# SCH_Blinking-led-tree-555_2025-11-29.net
KiCad netlist of a schematic drawn in EasyEDA
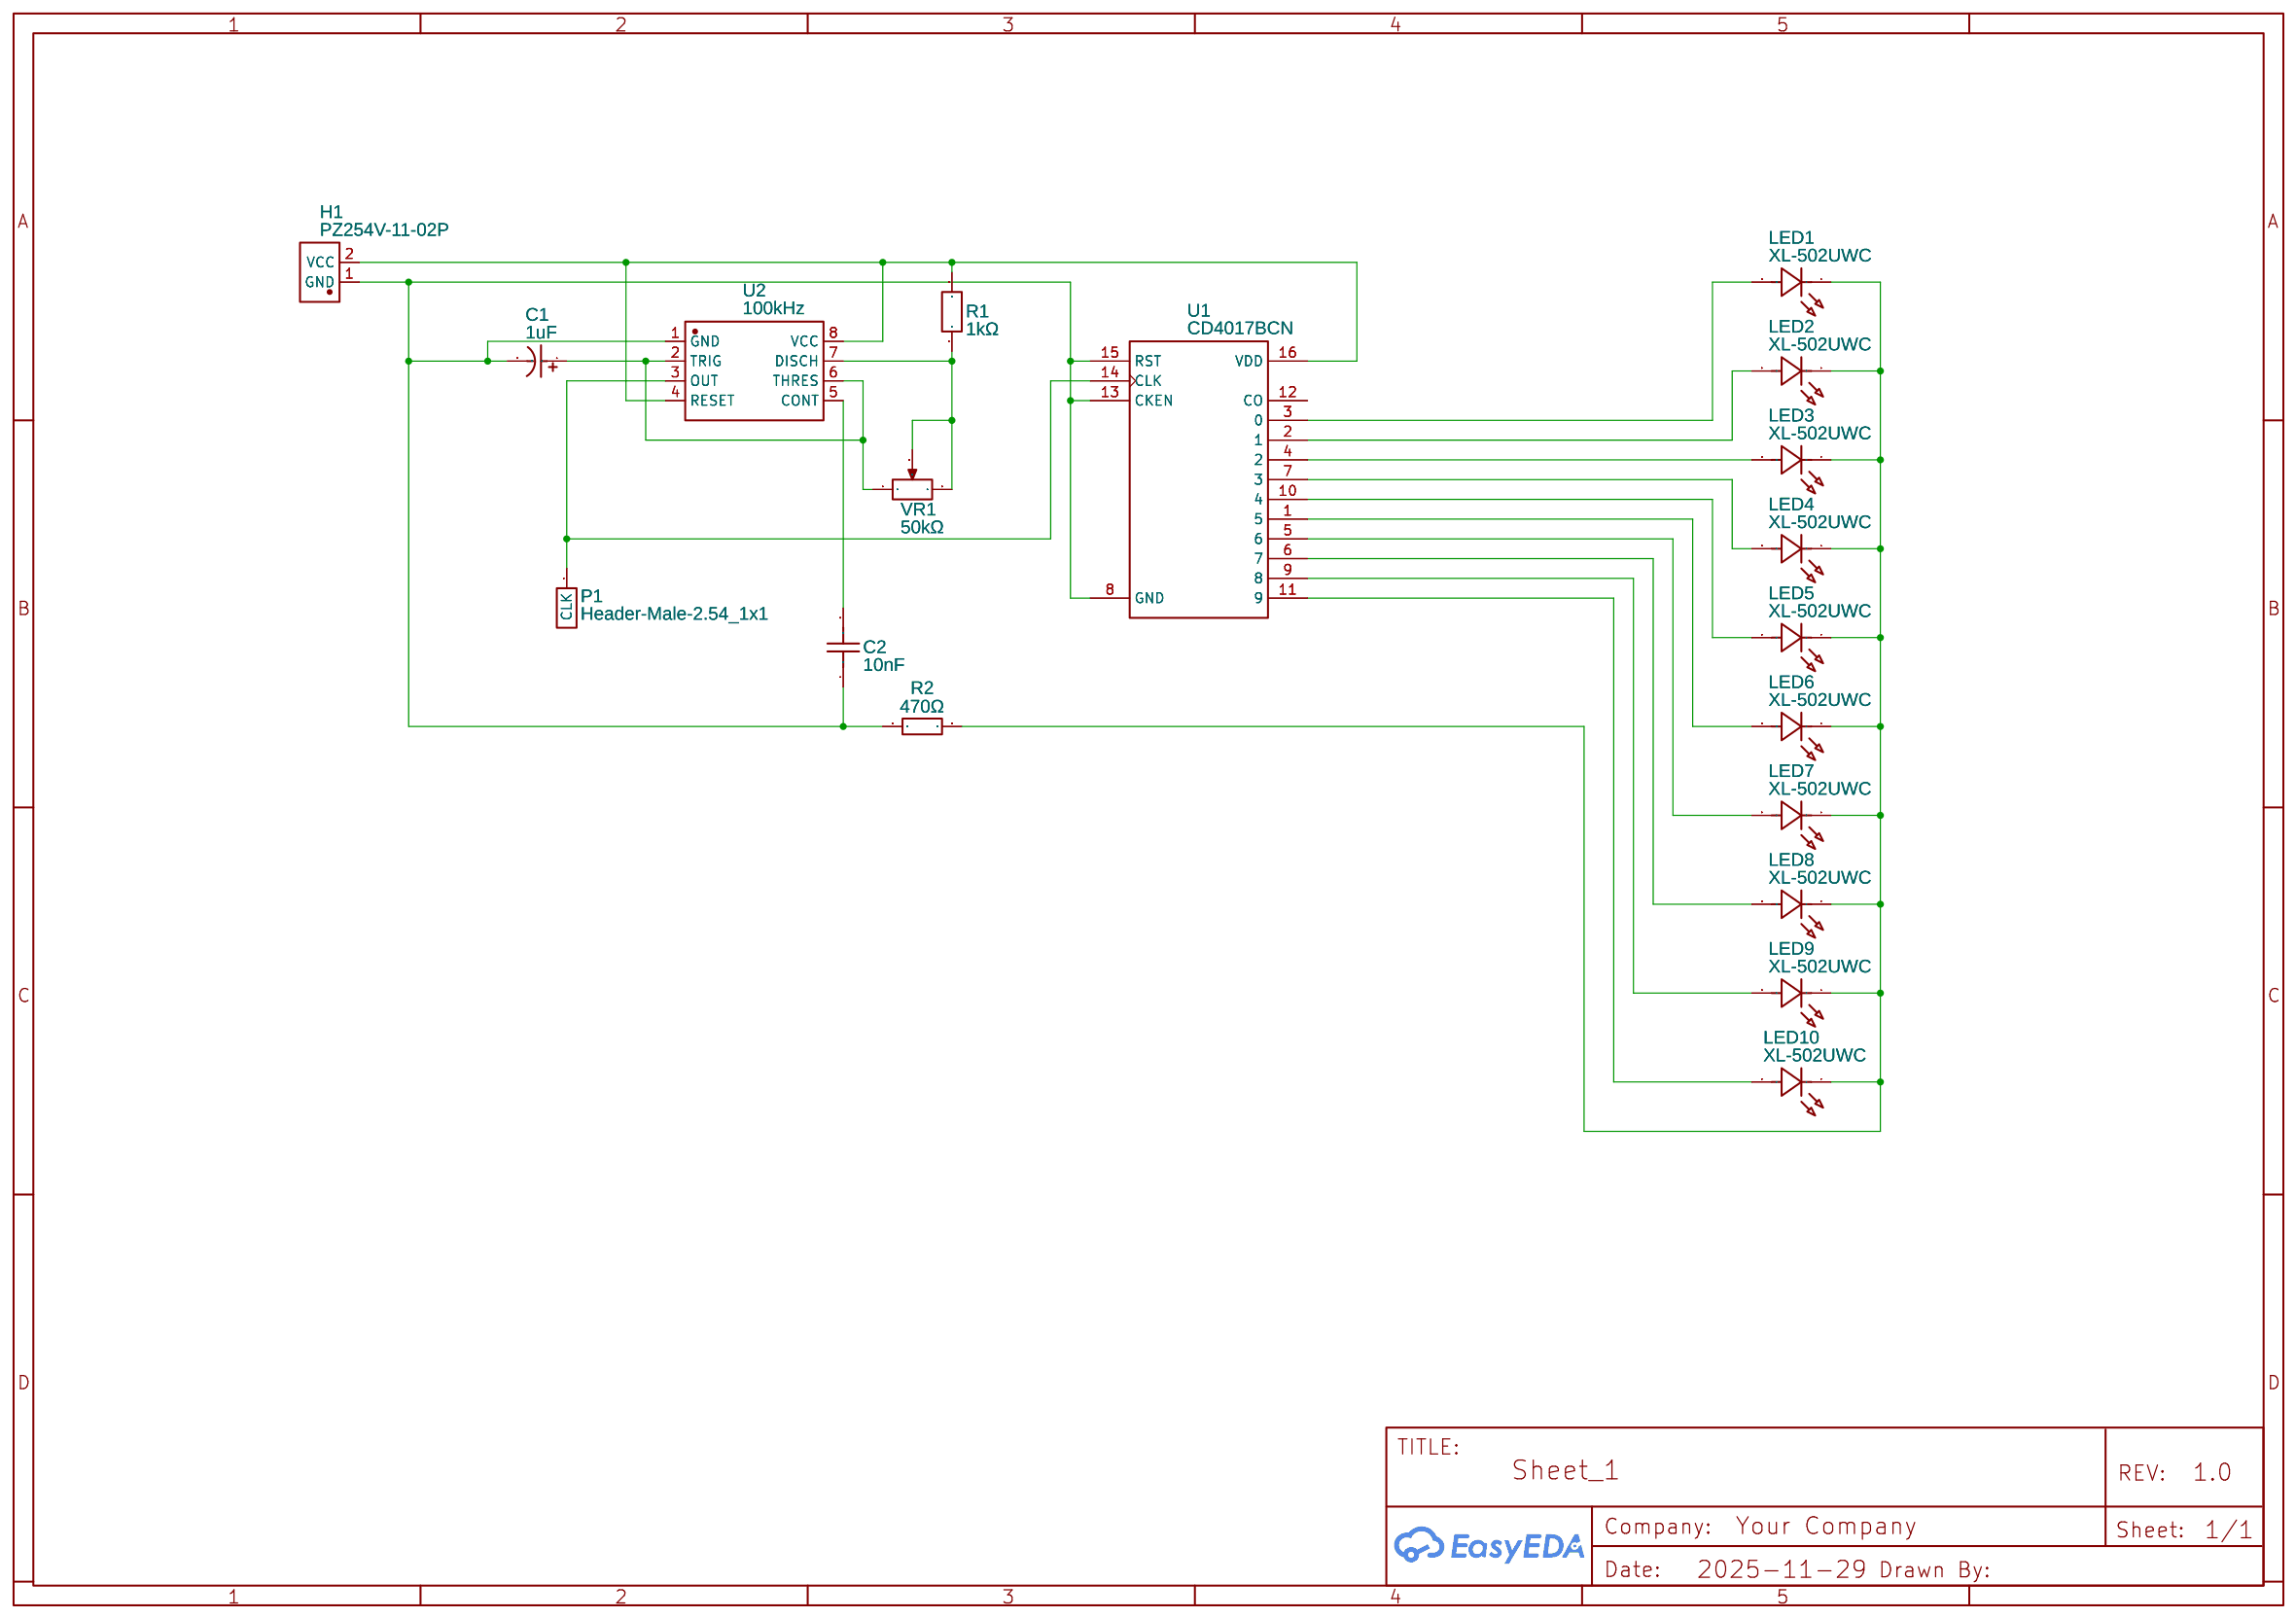
[diagram p0: schematic sheet]

(export (version "E")
  (design (tool "Eeschema 10.0.6"))
  (components
    (comp (ref "C1")
      (value "1uF")
      (fields (field (name "Manufacturer Part") "KF010M050C110A") (field (name "Manufacturer") "CapXon(丰宾)"))
      (libsource (lib "") (part "KF010M050C110A"))
    )
    (comp (ref "C2")
      (value "10nF")
      (fields (field (name "Manufacturer Part") "N09F1B103MN0B0S0N0") (field (name "Manufacturer") "STE(松田)"))
      (libsource (lib "") (part "N09F1B103MN0B0S0N0"))
    )
    (comp (ref "H1")
      (value "PZ254V-11-02P")
      (fields (field (name "Manufacturer") "XFCN(兴飞)"))
      (libsource (lib "") (part "PZ254V-11-02P"))
    )
    (comp (ref "LED1")
      (value "XL-502UWC")
      (fields (field (name "Manufacturer") "XINGLIGHT(成兴光)"))
      (libsource (lib "") (part "XL-502UWC"))
    )
    (comp (ref "LED2")
      (value "XL-502UWC")
      (fields (field (name "Manufacturer") "XINGLIGHT(成兴光)"))
      (libsource (lib "") (part "XL-502UWC"))
    )
    (comp (ref "LED3")
      (value "XL-502UWC")
      (fields (field (name "Manufacturer") "XINGLIGHT(成兴光)"))
      (libsource (lib "") (part "XL-502UWC"))
    )
    (comp (ref "LED4")
      (value "XL-502UWC")
      (fields (field (name "Manufacturer") "XINGLIGHT(成兴光)"))
      (libsource (lib "") (part "XL-502UWC"))
    )
    (comp (ref "LED5")
      (value "XL-502UWC")
      (fields (field (name "Manufacturer") "XINGLIGHT(成兴光)"))
      (libsource (lib "") (part "XL-502UWC"))
    )
    (comp (ref "LED6")
      (value "XL-502UWC")
      (fields (field (name "Manufacturer") "XINGLIGHT(成兴光)"))
      (libsource (lib "") (part "XL-502UWC"))
    )
    (comp (ref "LED7")
      (value "XL-502UWC")
      (fields (field (name "Manufacturer") "XINGLIGHT(成兴光)"))
      (libsource (lib "") (part "XL-502UWC"))
    )
    (comp (ref "LED8")
      (value "XL-502UWC")
      (fields (field (name "Manufacturer") "XINGLIGHT(成兴光)"))
      (libsource (lib "") (part "XL-502UWC"))
    )
    (comp (ref "LED9")
      (value "XL-502UWC")
      (fields (field (name "Manufacturer") "XINGLIGHT(成兴光)"))
      (libsource (lib "") (part "XL-502UWC"))
    )
    (comp (ref "LED10")
      (value "XL-502UWC")
      (fields (field (name "Manufacturer") "XINGLIGHT(成兴光)"))
      (libsource (lib "") (part "XL-502UWC"))
    )
    (comp (ref "P1")
      (value "Header-Male-2.54_1x1")
      (fields (field (name "Manufacturer Part") "2.54-1*1P针") (field (name "Manufacturer") "BOOMELE(博穆精密)"))
      (libsource (lib "") (part "Header-Male-2.54_1x1"))
    )
    (comp (ref "R1")
      (value "1kΩ")
      (fields (field (name "Manufacturer Part") "MF1/4W-1KΩ±1%T52") (field (name "Manufacturer") "华星机电"))
      (libsource (lib "") (part "MF1/4W-1KΩ±1%T52"))
    )
    (comp (ref "R2")
      (value "470Ω")
      (fields
        (field (name "Manufacturer Part") "MFR0W4F4700A50")
        (field (name "Manufacturer") "UNI-ROYAL(厚声)")
      )
      (libsource (lib "") (part "MFR0W4F4700A50"))
    )
    (comp (ref "U1") (value "CD4017BCN") (libsource (lib "") (part "CD4017BCN")))
    (comp (ref "U2")
      (value "100kHz")
      (fields (field (name "Manufacturer Part") "NE555P") (field (name "Manufacturer") "TI(德州仪器)"))
      (libsource (lib "") (part "NE555P"))
    )
    (comp (ref "VR1")
      (value "50kΩ")
      (fields (field (name "Manufacturer Part") "3296X-1-503") (field (name "Manufacturer") "BOCHEN(博晨)"))
      (libsource (lib "") (part "3296X-1-503_C118912"))
    )
  )
  (nets
    (net (code "1") (name "Net-(H1-GND)") (class "Default")
      (node (ref "C1") (pin "2") (pinfunction "2_2") (pintype "input"))
      (node (ref "C2") (pin "1") (pinfunction "1_1") (pintype "unspecified"))
      (node (ref "H1") (pin "1") (pinfunction "GND_1") (pintype "unspecified"))
      (node (ref "R2") (pin "1") (pinfunction "1_1") (pintype "input"))
      (node (ref "U1") (pin "13") (pinfunction "CKEN_13") (pintype "unspecified"))
      (node (ref "U1") (pin "15") (pinfunction "RST_15") (pintype "unspecified"))
      (node (ref "U1") (pin "8") (pinfunction "GND_8") (pintype "passive"))
      (node (ref "U2") (pin "1") (pinfunction "GND_1") (pintype "unspecified"))
    )
    (net (code "2") (name "Net-(H1-VCC)") (class "Default")
      (node (ref "H1") (pin "2") (pinfunction "VCC_2") (pintype "unspecified"))
      (node (ref "R1") (pin "2") (pinfunction "2_2") (pintype "unspecified"))
      (node (ref "U1") (pin "16") (pinfunction "VDD_16") (pintype "passive"))
      (node (ref "U2") (pin "4") (pinfunction "RESET_4") (pintype "unspecified"))
      (node (ref "U2") (pin "8") (pinfunction "VCC_8") (pintype "unspecified"))
    )
    (net (code "3") (name "Net-(LED1-A)") (class "Default")
      (node (ref "LED1") (pin "2") (pinfunction "A_2") (pintype "unspecified"))
      (node (ref "U1") (pin "3") (pinfunction "0_3") (pintype "output"))
    )
    (net (code "4") (name "Net-(LED1-K)") (class "Default")
      (node (ref "LED1") (pin "1") (pinfunction "K_1") (pintype "unspecified"))
      (node (ref "LED10") (pin "1") (pinfunction "K_1") (pintype "unspecified"))
      (node (ref "LED2") (pin "1") (pinfunction "K_1") (pintype "unspecified"))
      (node (ref "LED3") (pin "1") (pinfunction "K_1") (pintype "unspecified"))
      (node (ref "LED4") (pin "1") (pinfunction "K_1") (pintype "unspecified"))
      (node (ref "LED5") (pin "1") (pinfunction "K_1") (pintype "unspecified"))
      (node (ref "LED6") (pin "1") (pinfunction "K_1") (pintype "unspecified"))
      (node (ref "LED7") (pin "1") (pinfunction "K_1") (pintype "unspecified"))
      (node (ref "LED8") (pin "1") (pinfunction "K_1") (pintype "unspecified"))
      (node (ref "LED9") (pin "1") (pinfunction "K_1") (pintype "unspecified"))
      (node (ref "R2") (pin "2") (pinfunction "2_2") (pintype "input"))
    )
    (net (code "5") (name "Net-(LED2-A)") (class "Default")
      (node (ref "LED2") (pin "2") (pinfunction "A_2") (pintype "unspecified"))
      (node (ref "U1") (pin "2") (pinfunction "1_2") (pintype "output"))
    )
    (net (code "6") (name "Net-(LED3-A)") (class "Default")
      (node (ref "LED3") (pin "2") (pinfunction "A_2") (pintype "unspecified"))
      (node (ref "U1") (pin "4") (pinfunction "2_4") (pintype "output"))
    )
    (net (code "7") (name "Net-(LED4-A)") (class "Default")
      (node (ref "LED4") (pin "2") (pinfunction "A_2") (pintype "unspecified"))
      (node (ref "U1") (pin "7") (pinfunction "3_7") (pintype "output"))
    )
    (net (code "8") (name "Net-(LED5-A)") (class "Default")
      (node (ref "LED5") (pin "2") (pinfunction "A_2") (pintype "unspecified"))
      (node (ref "U1") (pin "10") (pinfunction "4_10") (pintype "output"))
    )
    (net (code "9") (name "Net-(LED6-A)") (class "Default")
      (node (ref "LED6") (pin "2") (pinfunction "A_2") (pintype "unspecified"))
      (node (ref "U1") (pin "1") (pinfunction "5_1") (pintype "output"))
    )
    (net (code "10") (name "Net-(LED7-A)") (class "Default")
      (node (ref "LED7") (pin "2") (pinfunction "A_2") (pintype "unspecified"))
      (node (ref "U1") (pin "5") (pinfunction "6_5") (pintype "output"))
    )
    (net (code "11") (name "Net-(LED8-A)") (class "Default")
      (node (ref "LED8") (pin "2") (pinfunction "A_2") (pintype "unspecified"))
      (node (ref "U1") (pin "6") (pinfunction "7_6") (pintype "output"))
    )
    (net (code "12") (name "Net-(LED9-A)") (class "Default")
      (node (ref "LED9") (pin "2") (pinfunction "A_2") (pintype "unspecified"))
      (node (ref "U1") (pin "9") (pinfunction "8_9") (pintype "output"))
    )
    (net (code "13") (name "Net-(LED10-A)") (class "Default")
      (node (ref "LED10") (pin "2") (pinfunction "A_2") (pintype "unspecified"))
      (node (ref "U1") (pin "11") (pinfunction "9_11") (pintype "output"))
    )
    (net (code "14") (name "Net-(P1-CLK)") (class "Default")
      (node (ref "P1") (pin "1") (pinfunction "CLK_1") (pintype "input"))
      (node (ref "U1") (pin "14") (pinfunction "CLK_14") (pintype "unspecified"))
      (node (ref "U2") (pin "3") (pinfunction "OUT_3") (pintype "unspecified"))
    )
    (net (code "15") (name "Net-(U2-CONT)") (class "Default")
      (node (ref "C2") (pin "2") (pinfunction "2_2") (pintype "unspecified"))
      (node (ref "U2") (pin "5") (pinfunction "CONT_5") (pintype "unspecified"))
    )
    (net (code "16") (name "Net-(U2-DISCH)") (class "Default")
      (node (ref "R1") (pin "1") (pinfunction "1_1") (pintype "unspecified"))
      (node (ref "U2") (pin "7") (pinfunction "DISCH_7") (pintype "unspecified"))
      (node (ref "VR1") (pin "2") (pinfunction "2_2") (pintype "input"))
      (node (ref "VR1") (pin "3") (pinfunction "3_3") (pintype "input"))
    )
    (net (code "17") (name "Net-(U2-THRES)") (class "Default")
      (node (ref "C1") (pin "1") (pinfunction "1_1") (pintype "input"))
      (node (ref "U2") (pin "2") (pinfunction "TRIG_2") (pintype "unspecified"))
      (node (ref "U2") (pin "6") (pinfunction "THRES_6") (pintype "unspecified"))
      (node (ref "VR1") (pin "1") (pinfunction "1_1") (pintype "input"))
    )
    (net (code "18") (name "unconnected-(U1-CO-Pad12)") (class "Default")
      (node (ref "U1") (pin "12") (pinfunction "CO_12") (pintype "output"))
    )
  )
)
